# logic_level_converter_BSS138.net
KiCad netlist of a schematic drawn in EAGLE
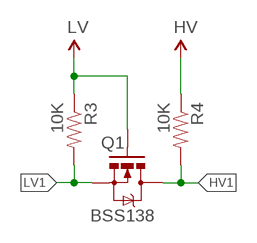
[diagram p0: schematic, sheet 1]

(export (version "E")
  (design (tool "Eeschema 10.0.6"))
  (components
    (comp (ref "Q1")
      (value "BSS138")
      (footprint "eagle-import:SOT23-3")
      (libsource (lib "eagle-import") (part "MOSFET-NCHANNELSMD"))
    )
    (comp (ref "R3")
      (value "10K")
      (footprint "eagle-import:0603-RES")
      (libsource (lib "eagle-import") (part "RESISTOR0603-RES"))
    )
    (comp (ref "R4")
      (value "10K")
      (footprint "eagle-import:0603-RES")
      (libsource (lib "eagle-import") (part "RESISTOR0603-RES"))
    )
  )
  (nets
    (net (code "1") (name "HV") (class "Default")
      (node (ref "R4") (pin "1") (pinfunction "1_1") (pintype "passive"))
    )
    (net (code "2") (name "HV1") (class "Default")
      (node (ref "Q1") (pin "3") (pinfunction "D_3") (pintype "passive"))
      (node (ref "R4") (pin "2") (pinfunction "2_2") (pintype "passive"))
    )
    (net (code "3") (name "LV") (class "Default")
      (node (ref "Q1") (pin "1") (pinfunction "G_1") (pintype "passive"))
      (node (ref "R3") (pin "1") (pinfunction "1_1") (pintype "passive"))
    )
    (net (code "4") (name "LV1") (class "Default")
      (node (ref "Q1") (pin "2") (pinfunction "S_2") (pintype "passive"))
      (node (ref "R3") (pin "2") (pinfunction "2_2") (pintype "passive"))
    )
  )
)
